# bl_interf.net
KiCad netlist of a schematic drawn in EAGLE
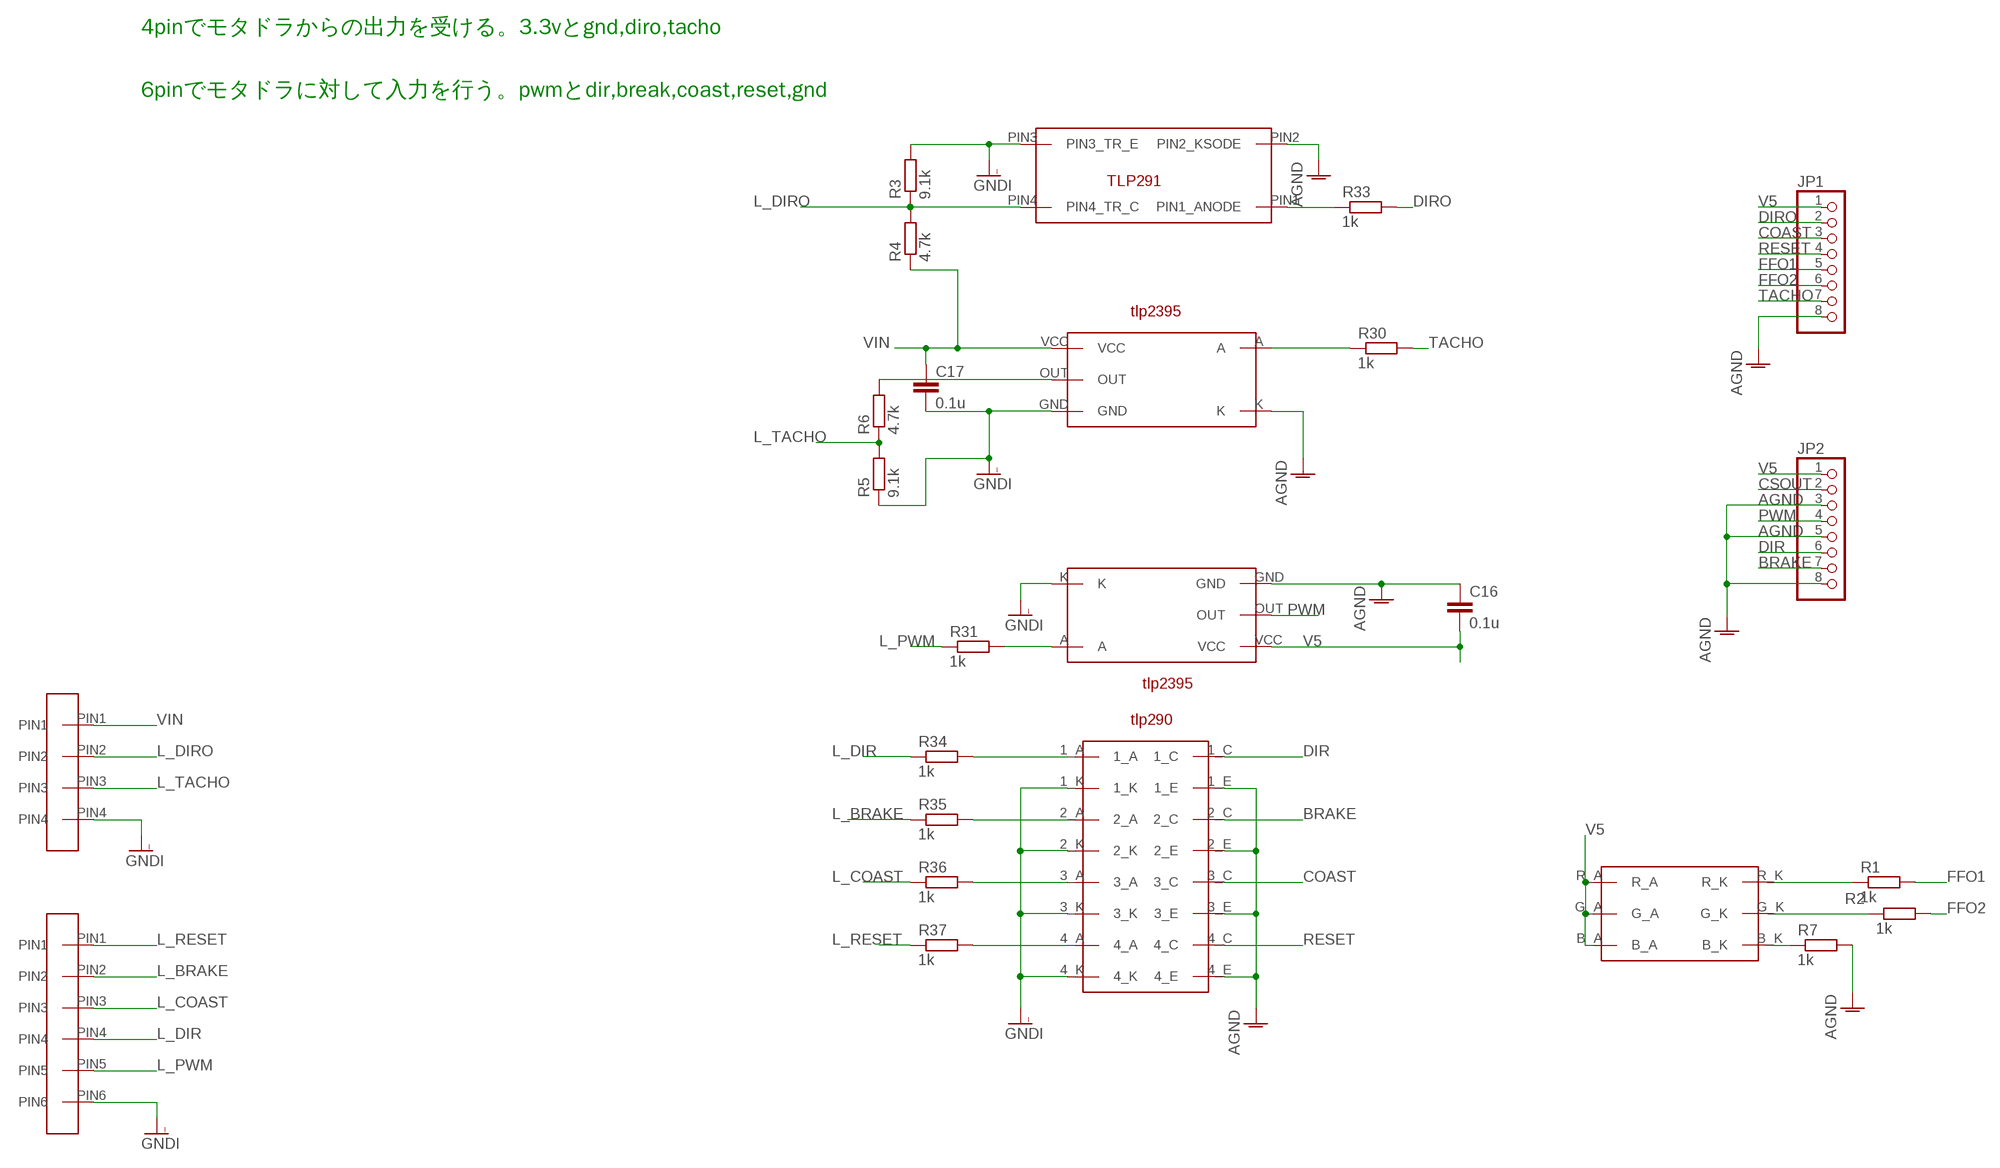
[diagram p0: schematic, sheet 1]

(export (version "E")
  (design (tool "Eeschema 10.0.6"))
  (components
    (comp (ref "C16")
      (value "0.1u")
      (footprint "eagle-import:C2012")
      (libsource (lib "eagle-import") (part "C-EUC2012"))
    )
    (comp (ref "C17")
      (value "0.1u")
      (footprint "eagle-import:C2012")
      (libsource (lib "eagle-import") (part "C-EUC2012"))
    )
    (comp (ref "JP1")
      (value "PINHD-1X8")
      (footprint "eagle-import:1X08")
      (libsource (lib "eagle-import") (part "PINHD-1X8"))
    )
    (comp (ref "JP2")
      (value "PINHD-1X8")
      (footprint "eagle-import:1X08")
      (libsource (lib "eagle-import") (part "PINHD-1X8"))
    )
    (comp (ref "R1")
      (value "1k")
      (footprint "eagle-import:M2012")
      (libsource (lib "eagle-import") (part "R-EU_M2012"))
    )
    (comp (ref "R2")
      (value "1k")
      (footprint "eagle-import:M2012")
      (libsource (lib "eagle-import") (part "R-EU_M2012"))
    )
    (comp (ref "R3")
      (value "9.1k")
      (footprint "eagle-import:M2012")
      (libsource (lib "eagle-import") (part "R-EU_M2012"))
    )
    (comp (ref "R4")
      (value "4.7k")
      (footprint "eagle-import:M2012")
      (libsource (lib "eagle-import") (part "R-EU_M2012"))
    )
    (comp (ref "R5")
      (value "9.1k")
      (footprint "eagle-import:M2012")
      (libsource (lib "eagle-import") (part "R-EU_M2012"))
    )
    (comp (ref "R6")
      (value "4.7k")
      (footprint "eagle-import:M2012")
      (libsource (lib "eagle-import") (part "R-EU_M2012"))
    )
    (comp (ref "R7")
      (value "1k")
      (footprint "eagle-import:M2012")
      (libsource (lib "eagle-import") (part "R-EU_M2012"))
    )
    (comp (ref "R30")
      (value "1k")
      (footprint "eagle-import:M2012")
      (libsource (lib "eagle-import") (part "R-EU_M2012"))
    )
    (comp (ref "R31")
      (value "1k")
      (footprint "eagle-import:M2012")
      (libsource (lib "eagle-import") (part "R-EU_M2012"))
    )
    (comp (ref "R33")
      (value "1k")
      (footprint "eagle-import:M2012")
      (libsource (lib "eagle-import") (part "R-EU_M2012"))
    )
    (comp (ref "R34")
      (value "1k")
      (footprint "eagle-import:M2012")
      (libsource (lib "eagle-import") (part "R-EU_M2012"))
    )
    (comp (ref "R35")
      (value "1k")
      (footprint "eagle-import:M2012")
      (libsource (lib "eagle-import") (part "R-EU_M2012"))
    )
    (comp (ref "R36")
      (value "1k")
      (footprint "eagle-import:M2012")
      (libsource (lib "eagle-import") (part "R-EU_M2012"))
    )
    (comp (ref "R37")
      (value "1k")
      (footprint "eagle-import:M2012")
      (libsource (lib "eagle-import") (part "R-EU_M2012"))
    )
    (comp (ref "U$1")
      (value "RGB_LED")
      (footprint "eagle-import:RGB_LED")
      (libsource (lib "eagle-import") (part "RGB_LED"))
    )
    (comp (ref "U$17")
      (value "TLP2395")
      (footprint "eagle-import:TLP2395")
      (libsource (lib "eagle-import") (part "TLP2395"))
    )
    (comp (ref "U$18")
      (value "TLP2395")
      (footprint "eagle-import:TLP2395")
      (libsource (lib "eagle-import") (part "TLP2395"))
    )
    (comp (ref "U$19")
      (value "TLP291")
      (footprint "eagle-import:TLP291")
      (libsource (lib "eagle-import") (part "TLP291"))
    )
    (comp (ref "U$20")
      (value "TLP290-4")
      (footprint "eagle-import:TLP290")
      (libsource (lib "eagle-import") (part "TLP290-4"))
    )
    (comp (ref "U$21")
      (value "DF1B_L_4P")
      (footprint "eagle-import:DF1B_L_4P")
      (libsource (lib "eagle-import") (part "DF1B_L_4P"))
    )
    (comp (ref "U$22")
      (value "DF1B_L_6P")
      (footprint "eagle-import:DF1B_L_6P")
      (libsource (lib "eagle-import") (part "DF1B_L_6P"))
    )
  )
  (nets
    (net (code "1") (name "/BRAKE") (class "Default")
      (node (ref "JP2") (pin "7") (pinfunction "7_7") (pintype "passive"))
      (node (ref "U$20") (pin "2_C") (pinfunction "2_C_2_C") (pintype "bidirectional"))
    )
    (net (code "2") (name "/COAST") (class "Default")
      (node (ref "JP1") (pin "3") (pinfunction "3_3") (pintype "passive"))
      (node (ref "U$20") (pin "3_C") (pinfunction "3_C_3_C") (pintype "bidirectional"))
    )
    (net (code "3") (name "/CSOUT") (class "Default")
      (node (ref "JP2") (pin "2") (pinfunction "2_2") (pintype "passive"))
    )
    (net (code "4") (name "/DIR") (class "Default")
      (node (ref "JP2") (pin "6") (pinfunction "6_6") (pintype "passive"))
      (node (ref "U$20") (pin "1_C") (pinfunction "1_C_1_C") (pintype "bidirectional"))
    )
    (net (code "5") (name "/DIRO") (class "Default")
      (node (ref "JP1") (pin "2") (pinfunction "2_2") (pintype "passive"))
      (node (ref "R33") (pin "2") (pinfunction "2_2") (pintype "passive"))
    )
    (net (code "6") (name "/FFO1") (class "Default")
      (node (ref "JP1") (pin "5") (pinfunction "5_5") (pintype "passive"))
      (node (ref "R1") (pin "2") (pinfunction "2_2") (pintype "passive"))
    )
    (net (code "7") (name "/FFO2") (class "Default")
      (node (ref "JP1") (pin "6") (pinfunction "6_6") (pintype "passive"))
      (node (ref "R2") (pin "2") (pinfunction "2_2") (pintype "passive"))
    )
    (net (code "8") (name "/L_BRAKE") (class "Default")
      (node (ref "R35") (pin "1") (pinfunction "1_1") (pintype "passive"))
      (node (ref "U$22") (pin "PIN2") (pinfunction "PIN2_PIN2") (pintype "bidirectional"))
    )
    (net (code "9") (name "/L_COAST") (class "Default")
      (node (ref "R36") (pin "1") (pinfunction "1_1") (pintype "passive"))
      (node (ref "U$22") (pin "PIN3") (pinfunction "PIN3_PIN3") (pintype "bidirectional"))
    )
    (net (code "10") (name "/L_DIR") (class "Default")
      (node (ref "R34") (pin "1") (pinfunction "1_1") (pintype "passive"))
      (node (ref "U$22") (pin "PIN4") (pinfunction "PIN4_PIN4") (pintype "bidirectional"))
    )
    (net (code "11") (name "/L_DIRO") (class "Default")
      (node (ref "R3") (pin "1") (pinfunction "1_1") (pintype "passive"))
      (node (ref "R4") (pin "2") (pinfunction "2_2") (pintype "passive"))
      (node (ref "U$19") (pin "PIN4") (pinfunction "PIN4_TR_C_PIN4") (pintype "bidirectional"))
      (node (ref "U$21") (pin "PIN2") (pinfunction "PIN2_PIN2") (pintype "bidirectional"))
    )
    (net (code "12") (name "/L_PWM") (class "Default")
      (node (ref "R31") (pin "1") (pinfunction "1_1") (pintype "passive"))
      (node (ref "U$22") (pin "PIN5") (pinfunction "PIN5_PIN5") (pintype "bidirectional"))
    )
    (net (code "13") (name "/L_RESET") (class "Default")
      (node (ref "R37") (pin "1") (pinfunction "1_1") (pintype "passive"))
      (node (ref "U$22") (pin "PIN1") (pinfunction "PIN1_PIN1") (pintype "bidirectional"))
    )
    (net (code "14") (name "/L_TACHO") (class "Default")
      (node (ref "R5") (pin "2") (pinfunction "2_2") (pintype "passive"))
      (node (ref "R6") (pin "1") (pinfunction "1_1") (pintype "passive"))
      (node (ref "U$21") (pin "PIN3") (pinfunction "PIN3_PIN3") (pintype "bidirectional"))
    )
    (net (code "15") (name "/PWM") (class "Default")
      (node (ref "JP2") (pin "4") (pinfunction "4_4") (pintype "passive"))
      (node (ref "U$18") (pin "OUT") (pinfunction "OUT_OUT") (pintype "bidirectional"))
    )
    (net (code "16") (name "/RESET") (class "Default")
      (node (ref "JP1") (pin "4") (pinfunction "4_4") (pintype "passive"))
      (node (ref "U$20") (pin "4_C") (pinfunction "4_C_4_C") (pintype "bidirectional"))
    )
    (net (code "17") (name "/TACHO") (class "Default")
      (node (ref "JP1") (pin "7") (pinfunction "7_7") (pintype "passive"))
      (node (ref "R30") (pin "2") (pinfunction "2_2") (pintype "passive"))
    )
    (net (code "18") (name "/V5") (class "Default")
      (node (ref "C16") (pin "2") (pinfunction "2_2") (pintype "passive"))
      (node (ref "JP1") (pin "1") (pinfunction "1_1") (pintype "passive"))
      (node (ref "JP2") (pin "1") (pinfunction "1_1") (pintype "passive"))
      (node (ref "U$1") (pin "B_A") (pinfunction "B_A_B_A") (pintype "bidirectional"))
      (node (ref "U$1") (pin "G_A") (pinfunction "G_A_G_A") (pintype "bidirectional"))
      (node (ref "U$1") (pin "R_A") (pinfunction "R_A_R_A") (pintype "bidirectional"))
      (node (ref "U$18") (pin "VCC") (pinfunction "VCC_VCC") (pintype "bidirectional"))
    )
    (net (code "19") (name "/VIN") (class "Default")
      (node (ref "C17") (pin "1") (pinfunction "1_1") (pintype "passive"))
      (node (ref "R4") (pin "1") (pinfunction "1_1") (pintype "passive"))
      (node (ref "U$17") (pin "VCC") (pinfunction "VCC_VCC") (pintype "bidirectional"))
      (node (ref "U$21") (pin "PIN1") (pinfunction "PIN1_PIN1") (pintype "bidirectional"))
    )
    (net (code "20") (name "AGND") (class "Default")
      (node (ref "C16") (pin "1") (pinfunction "1_1") (pintype "passive"))
      (node (ref "JP1") (pin "8") (pinfunction "8_8") (pintype "passive"))
      (node (ref "JP2") (pin "3") (pinfunction "3_3") (pintype "passive"))
      (node (ref "JP2") (pin "5") (pinfunction "5_5") (pintype "passive"))
      (node (ref "JP2") (pin "8") (pinfunction "8_8") (pintype "passive"))
      (node (ref "R7") (pin "2") (pinfunction "2_2") (pintype "passive"))
      (node (ref "U$17") (pin "K") (pinfunction "K_K") (pintype "bidirectional"))
      (node (ref "U$18") (pin "GND") (pinfunction "GND_GND") (pintype "bidirectional"))
      (node (ref "U$19") (pin "PIN2") (pinfunction "PIN2_KSODE_PIN2") (pintype "bidirectional"))
      (node (ref "U$20") (pin "1_E") (pinfunction "1_E_1_E") (pintype "bidirectional"))
      (node (ref "U$20") (pin "2_E") (pinfunction "2_E_2_E") (pintype "bidirectional"))
      (node (ref "U$20") (pin "3_E") (pinfunction "3_E_3_E") (pintype "bidirectional"))
      (node (ref "U$20") (pin "4_E") (pinfunction "4_E_4_E") (pintype "bidirectional"))
    )
    (net (code "21") (name "GNDI") (class "Default")
      (node (ref "C17") (pin "2") (pinfunction "2_2") (pintype "passive"))
      (node (ref "R3") (pin "2") (pinfunction "2_2") (pintype "passive"))
      (node (ref "R5") (pin "1") (pinfunction "1_1") (pintype "passive"))
      (node (ref "U$17") (pin "GND") (pinfunction "GND_GND") (pintype "bidirectional"))
      (node (ref "U$18") (pin "K") (pinfunction "K_K") (pintype "bidirectional"))
      (node (ref "U$19") (pin "PIN3") (pinfunction "PIN3_TR_E_PIN3") (pintype "bidirectional"))
      (node (ref "U$20") (pin "1_K") (pinfunction "1_K_1_K") (pintype "bidirectional"))
      (node (ref "U$20") (pin "2_K") (pinfunction "2_K_2_K") (pintype "bidirectional"))
      (node (ref "U$20") (pin "3_K") (pinfunction "3_K_3_K") (pintype "bidirectional"))
      (node (ref "U$20") (pin "4_K") (pinfunction "4_K_4_K") (pintype "bidirectional"))
      (node (ref "U$21") (pin "PIN4") (pinfunction "PIN4_PIN4") (pintype "bidirectional"))
      (node (ref "U$22") (pin "PIN6") (pinfunction "PIN6_PIN6") (pintype "bidirectional"))
    )
    (net (code "22") (name "Net-(R1-Pad1)") (class "Default")
      (node (ref "R1") (pin "1") (pinfunction "1_1") (pintype "passive"))
      (node (ref "U$1") (pin "R_K") (pinfunction "R_K_R_K") (pintype "bidirectional"))
    )
    (net (code "23") (name "Net-(R2-Pad1)") (class "Default")
      (node (ref "R2") (pin "1") (pinfunction "1_1") (pintype "passive"))
      (node (ref "U$1") (pin "G_K") (pinfunction "G_K_G_K") (pintype "bidirectional"))
    )
    (net (code "24") (name "Net-(R6-Pad2)") (class "Default")
      (node (ref "R6") (pin "2") (pinfunction "2_2") (pintype "passive"))
      (node (ref "U$17") (pin "OUT") (pinfunction "OUT_OUT") (pintype "bidirectional"))
    )
    (net (code "25") (name "Net-(R7-Pad1)") (class "Default")
      (node (ref "R7") (pin "1") (pinfunction "1_1") (pintype "passive"))
      (node (ref "U$1") (pin "B_K") (pinfunction "B_K_B_K") (pintype "bidirectional"))
    )
    (net (code "26") (name "Net-(R30-Pad1)") (class "Default")
      (node (ref "R30") (pin "1") (pinfunction "1_1") (pintype "passive"))
      (node (ref "U$17") (pin "A") (pinfunction "A_A") (pintype "bidirectional"))
    )
    (net (code "27") (name "Net-(R31-Pad2)") (class "Default")
      (node (ref "R31") (pin "2") (pinfunction "2_2") (pintype "passive"))
      (node (ref "U$18") (pin "A") (pinfunction "A_A") (pintype "bidirectional"))
    )
    (net (code "28") (name "Net-(R34-Pad2)") (class "Default")
      (node (ref "R34") (pin "2") (pinfunction "2_2") (pintype "passive"))
      (node (ref "U$20") (pin "1_A") (pinfunction "1_A_1_A") (pintype "bidirectional"))
    )
    (net (code "29") (name "Net-(R35-Pad2)") (class "Default")
      (node (ref "R35") (pin "2") (pinfunction "2_2") (pintype "passive"))
      (node (ref "U$20") (pin "2_A") (pinfunction "2_A_2_A") (pintype "bidirectional"))
    )
    (net (code "30") (name "Net-(R36-Pad2)") (class "Default")
      (node (ref "R36") (pin "2") (pinfunction "2_2") (pintype "passive"))
      (node (ref "U$20") (pin "3_A") (pinfunction "3_A_3_A") (pintype "bidirectional"))
    )
    (net (code "31") (name "Net-(R37-Pad2)") (class "Default")
      (node (ref "R37") (pin "2") (pinfunction "2_2") (pintype "passive"))
      (node (ref "U$20") (pin "4_A") (pinfunction "4_A_4_A") (pintype "bidirectional"))
    )
    (net (code "32") (name "Net-(U$19-PIN1_ANODE)") (class "Default")
      (node (ref "R33") (pin "1") (pinfunction "1_1") (pintype "passive"))
      (node (ref "U$19") (pin "PIN1") (pinfunction "PIN1_ANODE_PIN1") (pintype "bidirectional"))
    )
  )
)
